# BoardIR.net
KiCad netlist of a schematic drawn in EAGLE
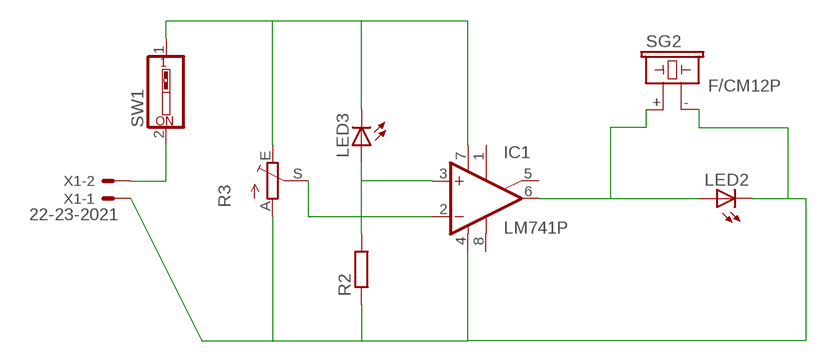
[diagram p0: schematic, sheet 1]

(export (version "E")
  (design (tool "Eeschema 10.0.6"))
  (components
    (comp (ref "IC1")
      (value "LM741P")
      (footprint "eagle-import:DIL08")
      (libsource (lib "eagle-import") (part "741PLM"))
    )
    (comp (ref "LED2")
      (value "LED5MM")
      (footprint "eagle-import:LED5MM")
      (libsource (lib "eagle-import") (part "LED5MM"))
    )
    (comp (ref "LED3")
      (value "LED5MM")
      (footprint "eagle-import:LED5MM")
      (libsource (lib "eagle-import") (part "LED5MM"))
    )
    (comp (ref "R2")
      (value "R-EU_0204/5")
      (footprint "eagle-import:0204_5")
      (libsource (lib "eagle-import") (part "R-EU_0204/5"))
    )
    (comp (ref "R3")
      (value "TRIM_EU-CA6V")
      (footprint "eagle-import:CA6V")
      (libsource (lib "eagle-import") (part "TRIM_EU-CA6V"))
    )
    (comp (ref "SG2")
      (value "F/CM12P")
      (footprint "eagle-import:F_CM12P")
      (libsource (lib "eagle-import") (part "F/CM12P"))
    )
    (comp (ref "SW1")
      (value "SW_DIP-1")
      (footprint "eagle-import:EDG-01")
      (libsource (lib "eagle-import") (part "SW_DIP-1"))
    )
    (comp (ref "X1")
      (value "22-23-2021")
      (footprint "eagle-import:22-23-2021")
      (fields (field (name "MF") "MOLEX"))
      (libsource (lib "eagle-import") (part "22-23-2021"))
    )
  )
  (nets
    (net (code "1") (name "Net-(IC1-+IN)") (class "Default")
      (node (ref "IC1") (pin "3") (pinfunction "+IN_3") (pintype "input"))
      (node (ref "LED3") (pin "A") (pinfunction "A_A") (pintype "passive"))
      (node (ref "R2") (pin "2") (pinfunction "2_2") (pintype "passive"))
    )
    (net (code "2") (name "Net-(IC1--IN)") (class "Default")
      (node (ref "IC1") (pin "2") (pinfunction "-IN_2") (pintype "input"))
      (node (ref "R3") (pin "S") (pinfunction "S_S") (pintype "passive"))
    )
    (net (code "3") (name "Net-(IC1-OUT)") (class "Default")
      (node (ref "IC1") (pin "6") (pinfunction "OUT_6") (pintype "output"))
      (node (ref "LED2") (pin "A") (pinfunction "A_A") (pintype "passive"))
      (node (ref "SG2") (pin "+") (pinfunction "1_+") (pintype "passive"))
    )
    (net (code "4") (name "Net-(IC1-V+)") (class "Default")
      (node (ref "IC1") (pin "7") (pinfunction "V+_7") (pintype "power_in"))
      (node (ref "LED3") (pin "K") (pinfunction "C_K") (pintype "passive"))
      (node (ref "R3") (pin "E") (pinfunction "E_E") (pintype "passive"))
      (node (ref "SW1") (pin "1") (pinfunction "1_1") (pintype "passive"))
    )
    (net (code "5") (name "Net-(IC1-V-)") (class "Default")
      (node (ref "IC1") (pin "4") (pinfunction "V-_4") (pintype "power_in"))
      (node (ref "LED2") (pin "K") (pinfunction "C_K") (pintype "passive"))
      (node (ref "R2") (pin "1") (pinfunction "1_1") (pintype "passive"))
      (node (ref "R3") (pin "A") (pinfunction "A_A") (pintype "passive"))
      (node (ref "SG2") (pin "-") (pinfunction "2_-") (pintype "passive"))
      (node (ref "X1") (pin "1") (pinfunction "S_1") (pintype "passive"))
    )
    (net (code "6") (name "Net-(X1B-S)") (class "Default")
      (node (ref "SW1") (pin "2") (pinfunction "2_2") (pintype "passive"))
      (node (ref "X1") (pin "2") (pinfunction "S_2") (pintype "passive"))
    )
    (net (code "7") (name "unconnected-(IC1-ON1-Pad1)") (class "Default")
      (node (ref "IC1") (pin "1") (pinfunction "ON1_1") (pintype "passive"))
    )
    (net (code "8") (name "unconnected-(IC1-ON2-Pad5)") (class "Default")
      (node (ref "IC1") (pin "5") (pinfunction "ON2_5") (pintype "passive"))
    )
    (net (code "9") (name "unconnected-(IC1-OPT-Pad8)") (class "Default")
      (node (ref "IC1") (pin "8") (pinfunction "OPT_8") (pintype "passive"))
    )
  )
)
